# relay.net
KiCad netlist of a schematic drawn in Altium Designer
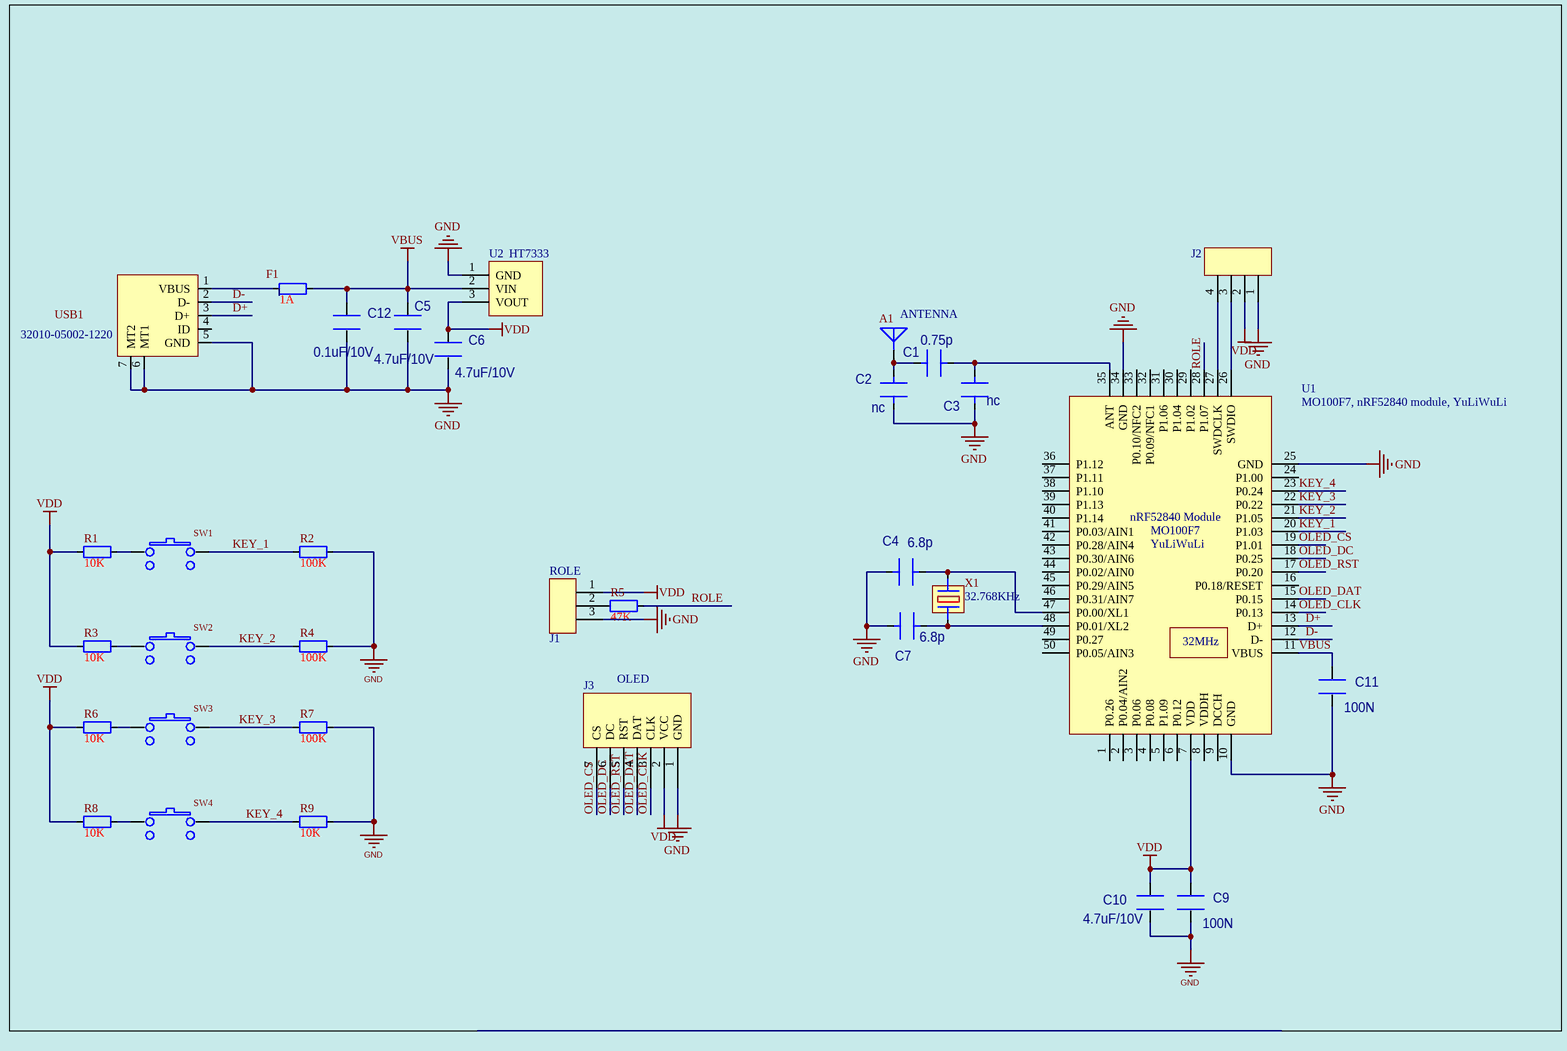
[diagram p0: relay.SchDoc]

(export (version "E")
  (design (tool "Eeschema 10.0.6"))
  (components
    (comp (ref "A1")
      (value "ANTENNA")
      (footprint "AN2")
      (description "PCB Antenna")
      (libsource (lib "switch") (part "ANTENNA"))
    )
    (comp (ref "C1")
      (value "0.75p")
      (footprint "cap0603(1608)")
      (fields (field (name "Comment") "CAP"))
      (libsource (lib "switch_tx") (part "CAP"))
    )
    (comp (ref "C2")
      (value "nc")
      (footprint "cap0603(1608)")
      (fields (field (name "Comment") "CAP"))
      (libsource (lib "switch_tx") (part "CAP"))
    )
    (comp (ref "C3")
      (value "nc")
      (footprint "cap0603(1608)")
      (fields (field (name "Comment") "CAP"))
      (libsource (lib "switch_tx") (part "CAP"))
    )
    (comp (ref "C4")
      (value "6.8p")
      (footprint "cap0603(1608)")
      (fields (field (name "Comment") "CAP"))
      (libsource (lib "switch_tx") (part "CAP"))
    )
    (comp (ref "C5")
      (value "4.7uF/10V")
      (footprint "cap0603(1608)")
      (fields (field (name "Comment") "CC103"))
      (libsource (lib "*") (part "CC103"))
    )
    (comp (ref "C6")
      (value "4.7uF/10V")
      (footprint "cap0603(1608)")
      (fields (field (name "Comment") "CC103"))
      (libsource (lib "*") (part "CC103"))
    )
    (comp (ref "C7")
      (value "6.8p")
      (footprint "cap0603(1608)")
      (fields (field (name "Comment") "CAP"))
      (libsource (lib "switch_tx") (part "CAP"))
    )
    (comp (ref "C9")
      (value "100N")
      (footprint "cap0603(1608)")
      (fields (field (name "Comment") "CC103"))
      (libsource (lib "*") (part "CC103"))
    )
    (comp (ref "C10")
      (value "4.7uF/10V")
      (footprint "cap0603(1608)")
      (fields (field (name "Comment") "CC103"))
      (libsource (lib "*") (part "CC103"))
    )
    (comp (ref "C11")
      (value "100N")
      (footprint "cap0603(1608)")
      (fields (field (name "Comment") "CC103"))
      (libsource (lib "*") (part "CC103"))
    )
    (comp (ref "C12")
      (value "0.1uF/10V")
      (footprint "cap0603(1608)")
      (fields (field (name "Comment") "CC103"))
      (libsource (lib "*") (part "CC103"))
    )
    (comp (ref "F1")
      (value "1A")
      (footprint "RESC0603(1608)_N")
      (fields (field (name "PUBLISHER") "i3tex"))
      (libsource (lib "switch_tx") (part "Res"))
    )
    (comp (ref "J1") (value "ROLE") (footprint "HEAD-1x3-2.54") (libsource (lib "vod") (part "HEAD-1x3")))
    (comp (ref "J2") (value "HEAD-1x4") (footprint "HEAD-1x4-2.54") (libsource (lib "vod") (part "HEAD-1x4")))
    (comp (ref "J3")
      (value "OLED")
      (footprint "OLED_mod_0.96_1")
      (libsource (lib "vod") (part "OLED_mod_0.96_1"))
    )
    (comp (ref "R1")
      (value "10K")
      (footprint "RESC0603(1608)_N")
      (fields (field (name "PUBLISHER") "i3tex"))
      (libsource (lib "switch_tx") (part "Res"))
    )
    (comp (ref "R2")
      (value "100K")
      (footprint "RESC0603(1608)_N")
      (fields (field (name "PUBLISHER") "i3tex"))
      (libsource (lib "switch_tx") (part "Res"))
    )
    (comp (ref "R3")
      (value "10K")
      (footprint "RESC0603(1608)_N")
      (fields (field (name "PUBLISHER") "i3tex"))
      (libsource (lib "switch_tx") (part "Res"))
    )
    (comp (ref "R4")
      (value "100K")
      (footprint "RESC0603(1608)_N")
      (fields (field (name "PUBLISHER") "i3tex"))
      (libsource (lib "") (part "Res_1"))
    )
    (comp (ref "R5")
      (value "47K")
      (footprint "RESC0603(1608)_N")
      (fields (field (name "PUBLISHER") "i3tex"))
      (libsource (lib "") (part "Res_1"))
    )
    (comp (ref "R6")
      (value "10K")
      (footprint "RESC0603(1608)_N")
      (fields (field (name "PUBLISHER") "i3tex"))
      (libsource (lib "switch_tx") (part "Res"))
    )
    (comp (ref "R7")
      (value "100K")
      (footprint "RESC0603(1608)_N")
      (fields (field (name "PUBLISHER") "i3tex"))
      (libsource (lib "switch_tx") (part "Res"))
    )
    (comp (ref "R8")
      (value "10K")
      (footprint "RESC0603(1608)_N")
      (fields (field (name "PUBLISHER") "i3tex"))
      (libsource (lib "switch_tx") (part "Res"))
    )
    (comp (ref "R9")
      (value "10K")
      (footprint "RESC0603(1608)_N")
      (fields (field (name "PUBLISHER") "i3tex"))
      (libsource (lib "switch_tx") (part "Res"))
    )
    (comp (ref "SW1")
      (value "TACT")
      (footprint "SW_6X6X5mm")
      (libsource (lib "Yihom_library") (part "SWITCH_TACT_SPST_2-2_PINS"))
    )
    (comp (ref "SW2")
      (value "TACT")
      (footprint "SW_6X6X5mm")
      (libsource (lib "Yihom_library") (part "SWITCH_TACT_SPST_2-2_PINS"))
    )
    (comp (ref "SW3")
      (value "TACT")
      (footprint "SW_6X6X5mm")
      (libsource (lib "Yihom_library") (part "SWITCH_TACT_SPST_2-2_PINS"))
    )
    (comp (ref "SW4")
      (value "TACT")
      (footprint "SW_6X6X5mm")
      (libsource (lib "Yihom_library") (part "SWITCH_TACT_SPST_2-2_PINS"))
    )
    (comp (ref "U1")
      (value "MO100F7, nRF52840 module, YuLiWuLi")
      (footprint "MO100F7")
      (libsource (lib "switch_tx") (part "MO100F7"))
    )
    (comp (ref "U2") (value "HT7333") (footprint "HT7333-SOT-89") (libsource (lib "vod") (part "HT7333")))
    (comp (ref "USB1")
      (value "32010-05002-1220")
      (footprint "Micro USB")
      (description "Mirco_USB_5S_B")
      (libsource (lib "USB_Connector") (part "Component_1"))
    )
    (comp (ref "X1")
      (value "32.768KHz")
      (footprint "32.768_A")
      (libsource (lib "switch_tx") (part "Crystal_2PIN"))
    )
  )
  (nets
    (net (code "1") (name "/D+") (class "Default")
      (node (ref "U1") (pin "13") (pinfunction "D+_13") (pintype "passive"))
      (node (ref "USB1") (pin "3") (pinfunction "D+_3") (pintype "passive"))
    )
    (net (code "2") (name "/D-") (class "Default")
      (node (ref "U1") (pin "12") (pinfunction "D-_12") (pintype "passive"))
      (node (ref "USB1") (pin "2") (pinfunction "D-_2") (pintype "passive"))
    )
    (net (code "3") (name "/KEY_1") (class "Default")
      (node (ref "R2") (pin "2") (pinfunction "2_2") (pintype "passive"))
      (node (ref "SW1") (pin "1") (pinfunction "1_1") (pintype "passive"))
      (node (ref "U1") (pin "20") (pinfunction "P1.03_20") (pintype "passive"))
    )
    (net (code "4") (name "/KEY_2") (class "Default")
      (node (ref "R4") (pin "1") (pinfunction "1_1") (pintype "passive"))
      (node (ref "SW2") (pin "1") (pinfunction "1_1") (pintype "passive"))
      (node (ref "U1") (pin "21") (pinfunction "P1.05_21") (pintype "passive"))
    )
    (net (code "5") (name "/KEY_3") (class "Default")
      (node (ref "R7") (pin "2") (pinfunction "2_2") (pintype "passive"))
      (node (ref "SW3") (pin "1") (pinfunction "1_1") (pintype "passive"))
      (node (ref "U1") (pin "22") (pinfunction "P0.22_22") (pintype "passive"))
    )
    (net (code "6") (name "/KEY_4") (class "Default")
      (node (ref "R9") (pin "2") (pinfunction "2_2") (pintype "passive"))
      (node (ref "SW4") (pin "1") (pinfunction "1_1") (pintype "passive"))
      (node (ref "U1") (pin "23") (pinfunction "P0.24_23") (pintype "passive"))
    )
    (net (code "7") (name "/OLED_CLK") (class "Default")
      (node (ref "J3") (pin "3") (pinfunction "CLK_3") (pintype "passive"))
      (node (ref "U1") (pin "14") (pinfunction "P0.13_14") (pintype "passive"))
    )
    (net (code "8") (name "/OLED_CS") (class "Default")
      (node (ref "J3") (pin "7") (pinfunction "CS_7") (pintype "passive"))
      (node (ref "U1") (pin "19") (pinfunction "P1.01_19") (pintype "passive"))
    )
    (net (code "9") (name "/OLED_DAT") (class "Default")
      (node (ref "J3") (pin "4") (pinfunction "DAT_4") (pintype "passive"))
      (node (ref "U1") (pin "15") (pinfunction "P0.15_15") (pintype "passive"))
    )
    (net (code "10") (name "/OLED_DC") (class "Default")
      (node (ref "J3") (pin "6") (pinfunction "DC_6") (pintype "passive"))
      (node (ref "U1") (pin "18") (pinfunction "P0.25_18") (pintype "passive"))
    )
    (net (code "11") (name "/OLED_RST") (class "Default")
      (node (ref "J3") (pin "5") (pinfunction "RST_5") (pintype "passive"))
      (node (ref "U1") (pin "17") (pinfunction "P0.20_17") (pintype "passive"))
    )
    (net (code "12") (name "/ROLE") (class "Default")
      (node (ref "R5") (pin "2") (pinfunction "2_2") (pintype "passive"))
      (node (ref "U1") (pin "28") (pinfunction "P1.07_28") (pintype "passive"))
    )
    (net (code "13") (name "GND") (class "Default")
      (node (ref "C10") (pin "2") (pinfunction "2_2") (pintype "passive"))
      (node (ref "C11") (pin "2") (pinfunction "2_2") (pintype "passive"))
      (node (ref "C12") (pin "2") (pinfunction "2_2") (pintype "passive"))
      (node (ref "C2") (pin "1") (pinfunction "1_1") (pintype "passive"))
      (node (ref "C3") (pin "2") (pinfunction "2_2") (pintype "passive"))
      (node (ref "C4") (pin "1") (pinfunction "1_1") (pintype "passive"))
      (node (ref "C5") (pin "2") (pinfunction "2_2") (pintype "passive"))
      (node (ref "C6") (pin "2") (pinfunction "2_2") (pintype "passive"))
      (node (ref "C7") (pin "1") (pinfunction "1_1") (pintype "passive"))
      (node (ref "C9") (pin "2") (pinfunction "2_2") (pintype "passive"))
      (node (ref "J1") (pin "3") (pintype "passive"))
      (node (ref "J2") (pin "1") (pintype "passive"))
      (node (ref "J3") (pin "1") (pinfunction "GND_1") (pintype "passive"))
      (node (ref "R2") (pin "1") (pinfunction "1_1") (pintype "passive"))
      (node (ref "R4") (pin "2") (pinfunction "2_2") (pintype "passive"))
      (node (ref "R7") (pin "1") (pinfunction "1_1") (pintype "passive"))
      (node (ref "R9") (pin "1") (pinfunction "1_1") (pintype "passive"))
      (node (ref "U1") (pin "10") (pinfunction "GND_10") (pintype "passive"))
      (node (ref "U1") (pin "25") (pinfunction "GND_25") (pintype "passive"))
      (node (ref "U1") (pin "34") (pinfunction "GND_34") (pintype "passive"))
      (node (ref "U2") (pin "1") (pinfunction "GND_1") (pintype "passive"))
      (node (ref "USB1") (pin "5") (pinfunction "GND_5") (pintype "passive"))
      (node (ref "USB1") (pin "6") (pinfunction "MT1_6") (pintype "passive"))
      (node (ref "USB1") (pin "7") (pinfunction "MT2_7") (pintype "passive"))
    )
    (net (code "14") (name "Net-(A1-A)") (class "Default")
      (node (ref "A1") (pin "1") (pinfunction "A_1") (pintype "passive"))
      (node (ref "C1") (pin "1") (pinfunction "1_1") (pintype "passive"))
      (node (ref "C2") (pin "2") (pinfunction "2_2") (pintype "passive"))
    )
    (net (code "15") (name "Net-(J1-Pad2)") (class "Default")
      (node (ref "J1") (pin "2") (pintype "passive"))
      (node (ref "R5") (pin "1") (pinfunction "1_1") (pintype "passive"))
    )
    (net (code "16") (name "Net-(R1-Pad1)") (class "Default")
      (node (ref "R1") (pin "1") (pinfunction "1_1") (pintype "passive"))
      (node (ref "SW1") (pin "2") (pinfunction "2_2") (pintype "passive"))
    )
    (net (code "17") (name "Net-(R3-Pad1)") (class "Default")
      (node (ref "R3") (pin "1") (pinfunction "1_1") (pintype "passive"))
      (node (ref "SW2") (pin "2") (pinfunction "2_2") (pintype "passive"))
    )
    (net (code "18") (name "Net-(R6-Pad1)") (class "Default")
      (node (ref "R6") (pin "1") (pinfunction "1_1") (pintype "passive"))
      (node (ref "SW3") (pin "2") (pinfunction "2_2") (pintype "passive"))
    )
    (net (code "19") (name "Net-(R8-Pad1)") (class "Default")
      (node (ref "R8") (pin "1") (pinfunction "1_1") (pintype "passive"))
      (node (ref "SW4") (pin "2") (pinfunction "2_2") (pintype "passive"))
    )
    (net (code "20") (name "Net-(U1-ANT)") (class "Default")
      (node (ref "C1") (pin "2") (pinfunction "2_2") (pintype "passive"))
      (node (ref "C3") (pin "1") (pinfunction "1_1") (pintype "passive"))
      (node (ref "U1") (pin "35") (pinfunction "ANT_35") (pintype "passive"))
    )
    (net (code "21") (name "Net-(U1-P0.00{slash}XL1)") (class "Default")
      (node (ref "C4") (pin "2") (pinfunction "2_2") (pintype "passive"))
      (node (ref "U1") (pin "47") (pinfunction "P0.00/XL1_47") (pintype "passive"))
      (node (ref "X1") (pin "2") (pinfunction "OUT_2") (pintype "passive"))
    )
    (net (code "22") (name "Net-(U1-P0.01{slash}XL2)") (class "Default")
      (node (ref "C7") (pin "2") (pinfunction "2_2") (pintype "passive"))
      (node (ref "U1") (pin "48") (pinfunction "P0.01/XL2_48") (pintype "passive"))
      (node (ref "X1") (pin "1") (pinfunction "IN_1") (pintype "passive"))
    )
    (net (code "23") (name "Net-(U1-SWDCLK)") (class "Default")
      (node (ref "J2") (pin "4") (pintype "passive"))
      (node (ref "U1") (pin "27") (pinfunction "SWDCLK_27") (pintype "passive"))
    )
    (net (code "24") (name "Net-(U1-SWDIO)") (class "Default")
      (node (ref "J2") (pin "3") (pintype "passive"))
      (node (ref "U1") (pin "26") (pinfunction "SWDIO_26") (pintype "passive"))
    )
    (net (code "25") (name "Net-(USB1-VBUS)") (class "Default")
      (node (ref "F1") (pin "2") (pinfunction "2_2") (pintype "passive"))
      (node (ref "USB1") (pin "1") (pinfunction "VBUS_1") (pintype "passive"))
    )
    (net (code "26") (name "VBUS") (class "Default")
      (node (ref "C11") (pin "1") (pinfunction "1_1") (pintype "passive"))
      (node (ref "C12") (pin "1") (pinfunction "1_1") (pintype "passive"))
      (node (ref "C5") (pin "1") (pinfunction "1_1") (pintype "passive"))
      (node (ref "F1") (pin "1") (pinfunction "1_1") (pintype "passive"))
      (node (ref "U1") (pin "11") (pinfunction "VBUS_11") (pintype "passive"))
      (node (ref "U2") (pin "2") (pinfunction "VIN_2") (pintype "passive"))
    )
    (net (code "27") (name "VDD") (class "Default")
      (node (ref "C10") (pin "1") (pinfunction "1_1") (pintype "passive"))
      (node (ref "C6") (pin "1") (pinfunction "1_1") (pintype "passive"))
      (node (ref "C9") (pin "1") (pinfunction "1_1") (pintype "passive"))
      (node (ref "J1") (pin "1") (pintype "passive"))
      (node (ref "J2") (pin "2") (pintype "passive"))
      (node (ref "J3") (pin "2") (pinfunction "VCC_2") (pintype "passive"))
      (node (ref "R1") (pin "2") (pinfunction "2_2") (pintype "passive"))
      (node (ref "R3") (pin "2") (pinfunction "2_2") (pintype "passive"))
      (node (ref "R6") (pin "2") (pinfunction "2_2") (pintype "passive"))
      (node (ref "R8") (pin "2") (pinfunction "2_2") (pintype "passive"))
      (node (ref "U1") (pin "7") (pinfunction "VDD_7") (pintype "passive"))
      (node (ref "U2") (pin "3") (pinfunction "VOUT_3") (pintype "passive"))
    )
    (net (code "28") (name "unconnected-(U1-DCCH-Pad9)") (class "Default")
      (node (ref "U1") (pin "9") (pinfunction "DCCH_9") (pintype "passive"))
    )
    (net (code "29") (name "unconnected-(U1-P0.02{slash}AIN0-Pad44)") (class "Default")
      (node (ref "U1") (pin "44") (pinfunction "P0.02/AIN0_44") (pintype "passive"))
    )
    (net (code "30") (name "unconnected-(U1-P0.03{slash}AIN1-Pad41)") (class "Default")
      (node (ref "U1") (pin "41") (pinfunction "P0.03/AIN1_41") (pintype "passive"))
    )
    (net (code "31") (name "unconnected-(U1-P0.04{slash}AIN2-Pad2)") (class "Default")
      (node (ref "U1") (pin "2") (pinfunction "P0.04/AIN2_2") (pintype "passive"))
    )
    (net (code "32") (name "unconnected-(U1-P0.05{slash}AIN3-Pad50)") (class "Default")
      (node (ref "U1") (pin "50") (pinfunction "P0.05/AIN3_50") (pintype "passive"))
    )
    (net (code "33") (name "unconnected-(U1-P0.06-Pad3)") (class "Default")
      (node (ref "U1") (pin "3") (pinfunction "P0.06_3") (pintype "passive"))
    )
    (net (code "34") (name "unconnected-(U1-P0.08-Pad4)") (class "Default")
      (node (ref "U1") (pin "4") (pinfunction "P0.08_4") (pintype "passive"))
    )
    (net (code "35") (name "unconnected-(U1-P0.09{slash}NFC1-Pad32)") (class "Default")
      (node (ref "U1") (pin "32") (pinfunction "P0.09/NFC1_32") (pintype "passive"))
    )
    (net (code "36") (name "unconnected-(U1-P0.10{slash}NFC2-Pad33)") (class "Default")
      (node (ref "U1") (pin "33") (pinfunction "P0.10/NFC2_33") (pintype "passive"))
    )
    (net (code "37") (name "unconnected-(U1-P0.12-Pad6)") (class "Default")
      (node (ref "U1") (pin "6") (pinfunction "P0.12_6") (pintype "passive"))
    )
    (net (code "38") (name "unconnected-(U1-P0.18{slash}RESET-Pad16)") (class "Default")
      (node (ref "U1") (pin "16") (pinfunction "P0.18/RESET_16") (pintype "passive"))
    )
    (net (code "39") (name "unconnected-(U1-P0.26-Pad1)") (class "Default")
      (node (ref "U1") (pin "1") (pinfunction "P0.26_1") (pintype "passive"))
    )
    (net (code "40") (name "unconnected-(U1-P0.27-Pad49)") (class "Default")
      (node (ref "U1") (pin "49") (pinfunction "P0.27_49") (pintype "passive"))
    )
    (net (code "41") (name "unconnected-(U1-P0.28{slash}AIN4-Pad42)") (class "Default")
      (node (ref "U1") (pin "42") (pinfunction "P0.28/AIN4_42") (pintype "passive"))
    )
    (net (code "42") (name "unconnected-(U1-P0.29{slash}AIN5-Pad45)") (class "Default")
      (node (ref "U1") (pin "45") (pinfunction "P0.29/AIN5_45") (pintype "passive"))
    )
    (net (code "43") (name "unconnected-(U1-P0.30{slash}AIN6-Pad43)") (class "Default")
      (node (ref "U1") (pin "43") (pinfunction "P0.30/AIN6_43") (pintype "passive"))
    )
    (net (code "44") (name "unconnected-(U1-P0.31{slash}AIN7-Pad46)") (class "Default")
      (node (ref "U1") (pin "46") (pinfunction "P0.31/AIN7_46") (pintype "passive"))
    )
    (net (code "45") (name "unconnected-(U1-P1.00-Pad24)") (class "Default")
      (node (ref "U1") (pin "24") (pinfunction "P1.00_24") (pintype "passive"))
    )
    (net (code "46") (name "unconnected-(U1-P1.02-Pad29)") (class "Default")
      (node (ref "U1") (pin "29") (pinfunction "P1.02_29") (pintype "passive"))
    )
    (net (code "47") (name "unconnected-(U1-P1.04-Pad30)") (class "Default")
      (node (ref "U1") (pin "30") (pinfunction "P1.04_30") (pintype "passive"))
    )
    (net (code "48") (name "unconnected-(U1-P1.06-Pad31)") (class "Default")
      (node (ref "U1") (pin "31") (pinfunction "P1.06_31") (pintype "passive"))
    )
    (net (code "49") (name "unconnected-(U1-P1.09-Pad5)") (class "Default")
      (node (ref "U1") (pin "5") (pinfunction "P1.09_5") (pintype "passive"))
    )
    (net (code "50") (name "unconnected-(U1-P1.10-Pad38)") (class "Default")
      (node (ref "U1") (pin "38") (pinfunction "P1.10_38") (pintype "passive"))
    )
    (net (code "51") (name "unconnected-(U1-P1.11-Pad37)") (class "Default")
      (node (ref "U1") (pin "37") (pinfunction "P1.11_37") (pintype "passive"))
    )
    (net (code "52") (name "unconnected-(U1-P1.12-Pad36)") (class "Default")
      (node (ref "U1") (pin "36") (pinfunction "P1.12_36") (pintype "passive"))
    )
    (net (code "53") (name "unconnected-(U1-P1.13-Pad39)") (class "Default")
      (node (ref "U1") (pin "39") (pinfunction "P1.13_39") (pintype "passive"))
    )
    (net (code "54") (name "unconnected-(U1-P1.14-Pad40)") (class "Default")
      (node (ref "U1") (pin "40") (pinfunction "P1.14_40") (pintype "passive"))
    )
    (net (code "55") (name "unconnected-(U1-VDDH-Pad8)") (class "Default")
      (node (ref "U1") (pin "8") (pinfunction "VDDH_8") (pintype "passive"))
    )
    (net (code "56") (name "unconnected-(USB1-ID-Pad4)") (class "Default")
      (node (ref "USB1") (pin "4") (pinfunction "ID_4") (pintype "passive"))
    )
  )
)
